# seletor.net
KiCad netlist of a schematic drawn in EAGLE
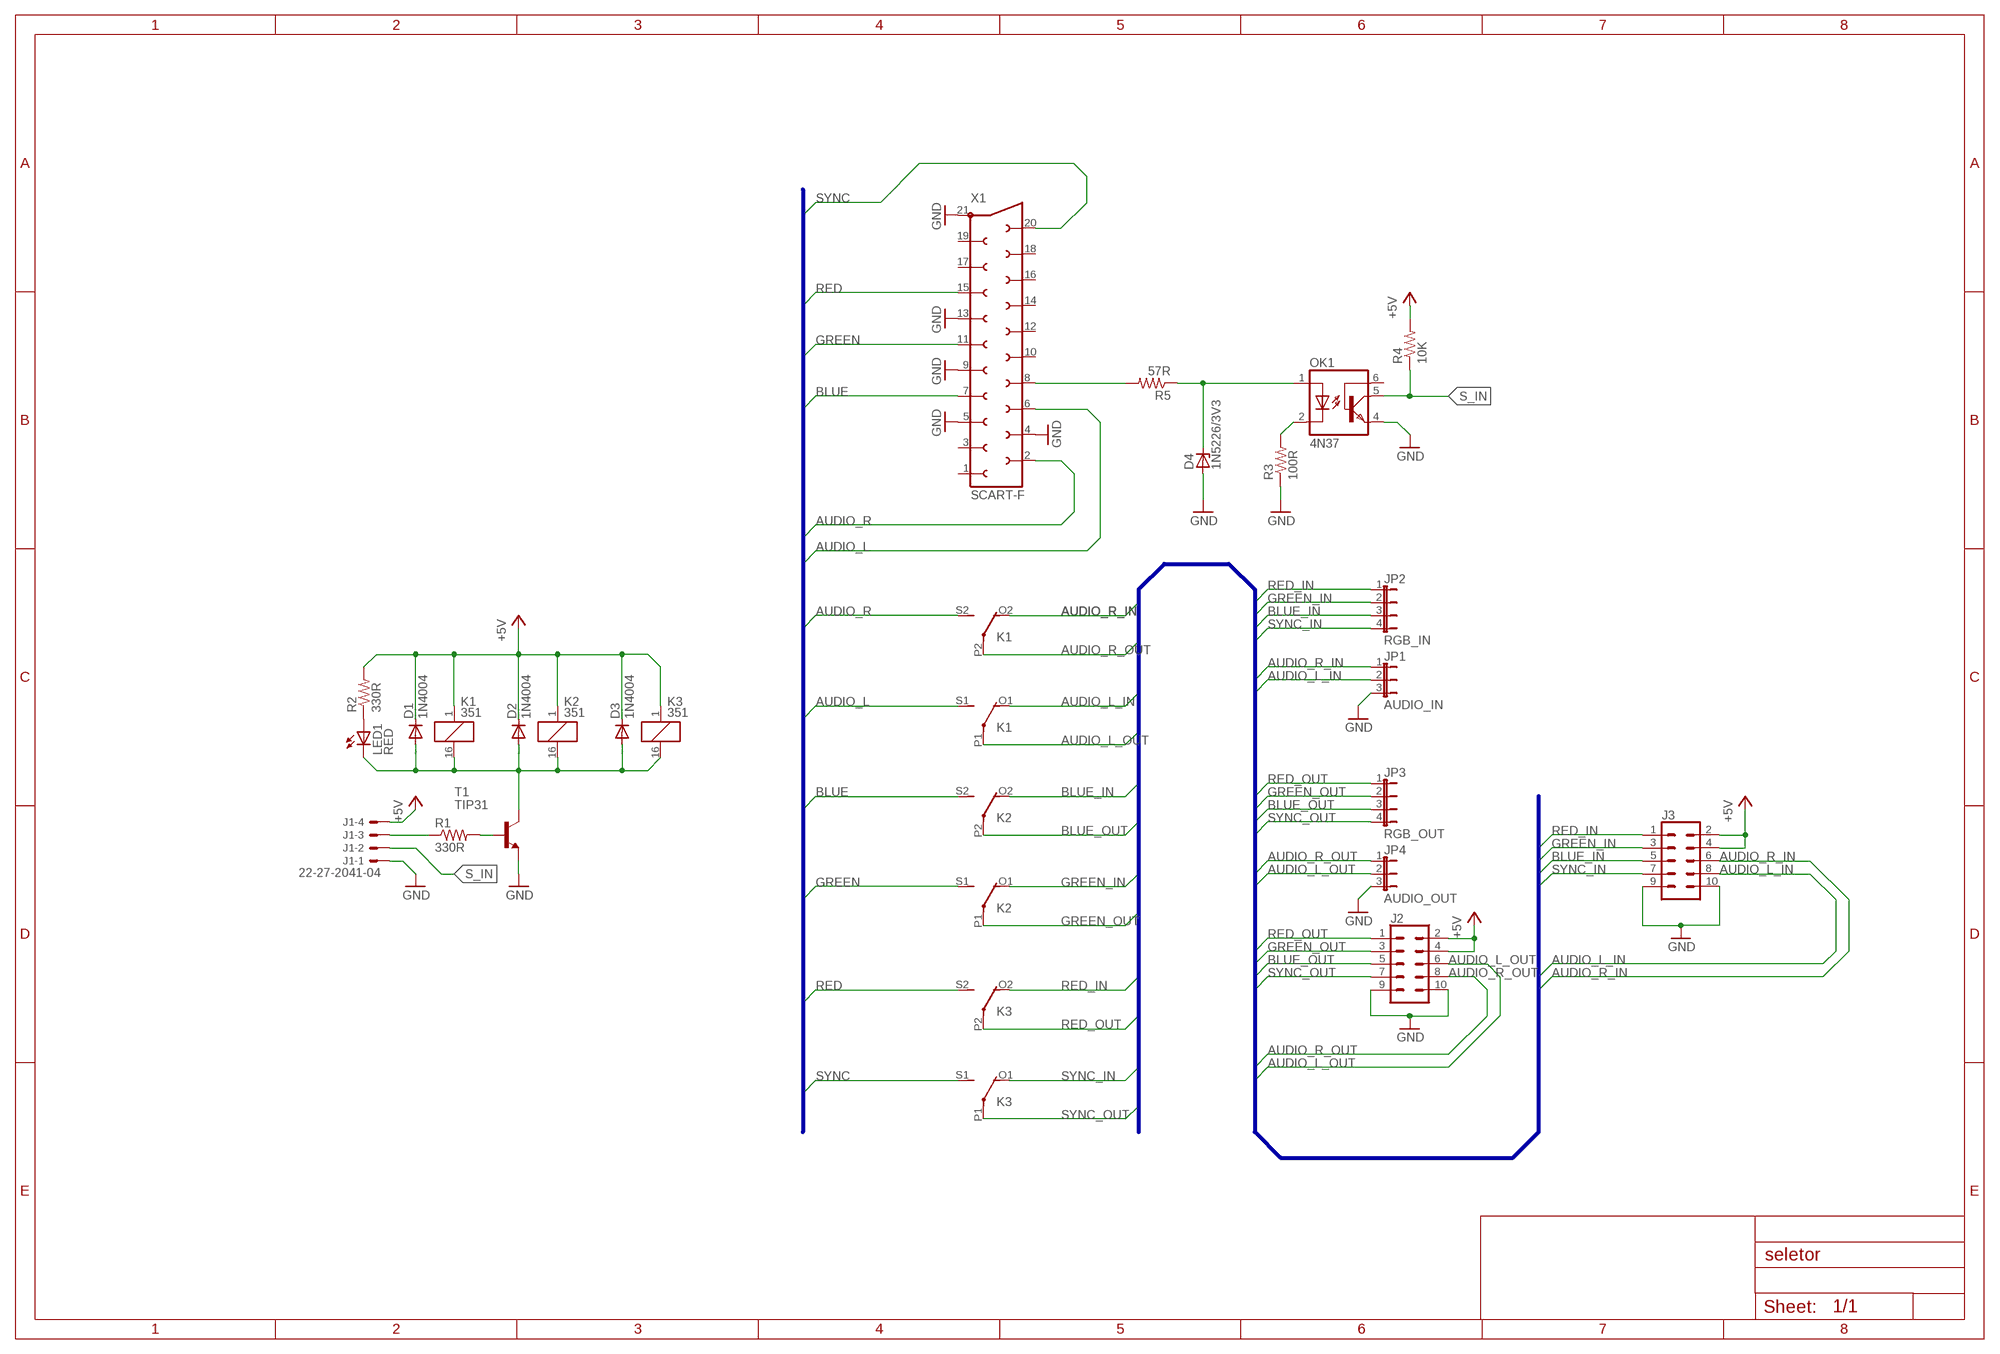
[diagram p0: schematic, sheet 1]

(export (version "E")
  (design (tool "Eeschema 10.0.6"))
  (components
    (comp (ref "D1")
      (value "1N4004")
      (footprint "eagle-import:DO41-10")
      (libsource (lib "eagle-import") (part "1N4004"))
    )
    (comp (ref "D2")
      (value "1N4004")
      (footprint "eagle-import:DO41-10")
      (libsource (lib "eagle-import") (part "1N4004"))
    )
    (comp (ref "D3")
      (value "1N4004")
      (footprint "eagle-import:DO41-10")
      (libsource (lib "eagle-import") (part "1N4004"))
    )
    (comp (ref "D4")
      (value "1N5226/3V3")
      (footprint "eagle-import:DO34Z7")
      (libsource (lib "eagle-import") (part "BZX90"))
    )
    (comp (ref "J1")
      (value "22-27-2041-04")
      (footprint "eagle-import:6410-04")
      (libsource (lib "eagle-import") (part "22-?-0427-2041"))
    )
    (comp (ref "J2")
      (value "CONN_05X2SHD-NS")
      (footprint "eagle-import:2X5-SHROUDED-NS")
      (libsource (lib "eagle-import") (part "CONN_05X2SHD-NS"))
    )
    (comp (ref "J3")
      (value "CONN_05X2SHD-NS")
      (footprint "eagle-import:2X5-SHROUDED-NS")
      (libsource (lib "eagle-import") (part "CONN_05X2SHD-NS"))
    )
    (comp (ref "JP1")
      (value "AUDIO_IN")
      (footprint "eagle-import:JP2")
      (libsource (lib "eagle-import") (part "JP2E"))
    )
    (comp (ref "JP2")
      (value "RGB_IN")
      (footprint "eagle-import:JP4")
      (libsource (lib "eagle-import") (part "JP4E"))
    )
    (comp (ref "JP3")
      (value "RGB_OUT")
      (footprint "eagle-import:JP4")
      (libsource (lib "eagle-import") (part "JP4E"))
    )
    (comp (ref "JP4")
      (value "AUDIO_OUT")
      (footprint "eagle-import:JP2")
      (libsource (lib "eagle-import") (part "JP2E"))
    )
    (comp (ref "K1")
      (value "351")
      (footprint "eagle-import:351")
      (libsource (lib "eagle-import") (part "351"))
    )
    (comp (ref "K2")
      (value "351")
      (footprint "eagle-import:351")
      (libsource (lib "eagle-import") (part "351"))
    )
    (comp (ref "K3")
      (value "351")
      (footprint "eagle-import:351")
      (libsource (lib "eagle-import") (part "351"))
    )
    (comp (ref "LED1")
      (value "RED")
      (footprint "eagle-import:LED5MM")
      (libsource (lib "eagle-import") (part "LED5MM"))
    )
    (comp (ref "OK1")
      (value "4N37")
      (footprint "eagle-import:DIL06")
      (fields (field (name "MF") "FAIRCHILD SEMICONDUCTOR"))
      (libsource (lib "eagle-import") (part "4N37"))
    )
    (comp (ref "R1")
      (value "330R")
      (footprint "eagle-import:0204_7")
      (libsource (lib "eagle-import") (part "R-US_0204/7"))
    )
    (comp (ref "R2")
      (value "330R")
      (footprint "eagle-import:0204_7")
      (libsource (lib "eagle-import") (part "R-US_0204/7"))
    )
    (comp (ref "R3")
      (value "100R")
      (footprint "eagle-import:0204_7")
      (libsource (lib "eagle-import") (part "resistor_R-US_0204/7"))
    )
    (comp (ref "R4")
      (value "10K")
      (footprint "eagle-import:0204_7")
      (libsource (lib "eagle-import") (part "resistor_R-US_0204/7"))
    )
    (comp (ref "R5")
      (value "57R")
      (footprint "eagle-import:0204_7")
      (libsource (lib "eagle-import") (part "R-US_0204/7"))
    )
    (comp (ref "T1")
      (value "TIP31")
      (footprint "eagle-import:TO220")
      (libsource (lib "eagle-import") (part "TIP31"))
    )
    (comp (ref "X1")
      (value "SCART-F")
      (footprint "eagle-import:SCART-F")
      (libsource (lib "eagle-import") (part "SCART-F"))
    )
  )
  (nets
    (net (code "1") (name "+5V") (class "Default")
      (node (ref "D1") (pin "C") (pinfunction "C_C") (pintype "passive"))
      (node (ref "D2") (pin "C") (pinfunction "C_C") (pintype "passive"))
      (node (ref "D3") (pin "C") (pinfunction "C_C") (pintype "passive"))
      (node (ref "J1") (pin "4") (pinfunction "S_4") (pintype "passive"))
      (node (ref "J2") (pin "2") (pinfunction "2_2") (pintype "passive"))
      (node (ref "J2") (pin "4") (pinfunction "4_4") (pintype "passive"))
      (node (ref "J3") (pin "2") (pinfunction "2_2") (pintype "passive"))
      (node (ref "J3") (pin "4") (pinfunction "4_4") (pintype "passive"))
      (node (ref "K1") (pin "1") (pinfunction "1_1") (pintype "passive"))
      (node (ref "K2") (pin "1") (pinfunction "1_1") (pintype "passive"))
      (node (ref "K3") (pin "1") (pinfunction "1_1") (pintype "passive"))
      (node (ref "R2") (pin "2") (pinfunction "2_2") (pintype "passive"))
      (node (ref "R4") (pin "2") (pinfunction "2_2") (pintype "passive"))
    )
    (net (code "2") (name "/AUDIO_L") (class "Default")
      (node (ref "K1") (pin "S1") (pinfunction "S_S1") (pintype "passive"))
      (node (ref "X1") (pin "6") (pinfunction "6_6") (pintype "passive"))
    )
    (net (code "3") (name "/AUDIO_L_IN") (class "Default")
      (node (ref "J3") (pin "8") (pinfunction "8_8") (pintype "passive"))
      (node (ref "JP1") (pin "2") (pinfunction "2_2") (pintype "passive"))
      (node (ref "K1") (pin "O1") (pinfunction "O_O1") (pintype "passive"))
    )
    (net (code "4") (name "/AUDIO_L_OUT") (class "Default")
      (node (ref "J2") (pin "6") (pinfunction "6_6") (pintype "passive"))
      (node (ref "JP4") (pin "2") (pinfunction "2_2") (pintype "passive"))
      (node (ref "K1") (pin "P1") (pinfunction "P_P1") (pintype "passive"))
    )
    (net (code "5") (name "/AUDIO_R") (class "Default")
      (node (ref "K1") (pin "S2") (pinfunction "S_S2") (pintype "passive"))
      (node (ref "X1") (pin "2") (pinfunction "2_2") (pintype "passive"))
    )
    (net (code "6") (name "/AUDIO_R_IN") (class "Default")
      (node (ref "J3") (pin "6") (pinfunction "6_6") (pintype "passive"))
      (node (ref "JP1") (pin "1") (pinfunction "1_1") (pintype "passive"))
      (node (ref "K1") (pin "O2") (pinfunction "O_O2") (pintype "passive"))
    )
    (net (code "7") (name "/AUDIO_R_OUT") (class "Default")
      (node (ref "J2") (pin "8") (pinfunction "8_8") (pintype "passive"))
      (node (ref "JP4") (pin "1") (pinfunction "1_1") (pintype "passive"))
      (node (ref "K1") (pin "P2") (pinfunction "P_P2") (pintype "passive"))
    )
    (net (code "8") (name "/BLUE") (class "Default")
      (node (ref "K2") (pin "S2") (pinfunction "S_S2") (pintype "passive"))
      (node (ref "X1") (pin "7") (pinfunction "7_7") (pintype "passive"))
    )
    (net (code "9") (name "/BLUE_IN") (class "Default")
      (node (ref "J3") (pin "5") (pinfunction "5_5") (pintype "passive"))
      (node (ref "JP2") (pin "3") (pinfunction "3_3") (pintype "passive"))
      (node (ref "K2") (pin "O2") (pinfunction "O_O2") (pintype "passive"))
    )
    (net (code "10") (name "/BLUE_OUT") (class "Default")
      (node (ref "J2") (pin "5") (pinfunction "5_5") (pintype "passive"))
      (node (ref "JP3") (pin "3") (pinfunction "3_3") (pintype "passive"))
      (node (ref "K2") (pin "P2") (pinfunction "P_P2") (pintype "passive"))
    )
    (net (code "11") (name "/GREEN") (class "Default")
      (node (ref "K2") (pin "S1") (pinfunction "S_S1") (pintype "passive"))
      (node (ref "X1") (pin "11") (pinfunction "11_11") (pintype "passive"))
    )
    (net (code "12") (name "/GREEN_IN") (class "Default")
      (node (ref "J3") (pin "3") (pinfunction "3_3") (pintype "passive"))
      (node (ref "JP2") (pin "2") (pinfunction "2_2") (pintype "passive"))
      (node (ref "K2") (pin "O1") (pinfunction "O_O1") (pintype "passive"))
    )
    (net (code "13") (name "/GREEN_OUT") (class "Default")
      (node (ref "J2") (pin "3") (pinfunction "3_3") (pintype "passive"))
      (node (ref "JP3") (pin "2") (pinfunction "2_2") (pintype "passive"))
      (node (ref "K2") (pin "P1") (pinfunction "P_P1") (pintype "passive"))
    )
    (net (code "14") (name "/RED") (class "Default")
      (node (ref "K3") (pin "S2") (pinfunction "S_S2") (pintype "passive"))
      (node (ref "X1") (pin "15") (pinfunction "15_15") (pintype "passive"))
    )
    (net (code "15") (name "/RED_IN") (class "Default")
      (node (ref "J3") (pin "1") (pinfunction "1_1") (pintype "passive"))
      (node (ref "JP2") (pin "1") (pinfunction "1_1") (pintype "passive"))
      (node (ref "K3") (pin "O2") (pinfunction "O_O2") (pintype "passive"))
    )
    (net (code "16") (name "/RED_OUT") (class "Default")
      (node (ref "J2") (pin "1") (pinfunction "1_1") (pintype "passive"))
      (node (ref "JP3") (pin "1") (pinfunction "1_1") (pintype "passive"))
      (node (ref "K3") (pin "P2") (pinfunction "P_P2") (pintype "passive"))
    )
    (net (code "17") (name "/SYNC") (class "Default")
      (node (ref "K3") (pin "S1") (pinfunction "S_S1") (pintype "passive"))
      (node (ref "X1") (pin "20") (pinfunction "20_20") (pintype "passive"))
    )
    (net (code "18") (name "/SYNC_IN") (class "Default")
      (node (ref "J3") (pin "7") (pinfunction "7_7") (pintype "passive"))
      (node (ref "JP2") (pin "4") (pinfunction "4_4") (pintype "passive"))
      (node (ref "K3") (pin "O1") (pinfunction "O_O1") (pintype "passive"))
    )
    (net (code "19") (name "/SYNC_OUT") (class "Default")
      (node (ref "J2") (pin "7") (pinfunction "7_7") (pintype "passive"))
      (node (ref "JP3") (pin "4") (pinfunction "4_4") (pintype "passive"))
      (node (ref "K3") (pin "P1") (pinfunction "P_P1") (pintype "passive"))
    )
    (net (code "20") (name "GND") (class "Default")
      (node (ref "D4") (pin "A") (pinfunction "A_A") (pintype "passive"))
      (node (ref "J1") (pin "1") (pinfunction "S_1") (pintype "passive"))
      (node (ref "J2") (pin "10") (pinfunction "10_10") (pintype "passive"))
      (node (ref "J2") (pin "9") (pinfunction "9_9") (pintype "passive"))
      (node (ref "J3") (pin "10") (pinfunction "10_10") (pintype "passive"))
      (node (ref "J3") (pin "9") (pinfunction "9_9") (pintype "passive"))
      (node (ref "JP1") (pin "3") (pinfunction "3_3") (pintype "passive"))
      (node (ref "JP4") (pin "3") (pinfunction "3_3") (pintype "passive"))
      (node (ref "OK1") (pin "4") (pinfunction "EMI_4") (pintype "passive"))
      (node (ref "R3") (pin "1") (pinfunction "1_1") (pintype "passive"))
      (node (ref "T1") (pin "3") (pinfunction "E_3") (pintype "passive"))
      (node (ref "X1") (pin "13") (pinfunction "13_13") (pintype "passive"))
      (node (ref "X1") (pin "21") (pinfunction "21_21") (pintype "passive"))
      (node (ref "X1") (pin "4") (pinfunction "4_4") (pintype "passive"))
      (node (ref "X1") (pin "5") (pinfunction "5_5") (pintype "passive"))
      (node (ref "X1") (pin "9") (pinfunction "9_9") (pintype "passive"))
    )
    (net (code "21") (name "Net-(J1C-S)") (class "Default")
      (node (ref "J1") (pin "3") (pinfunction "S_3") (pintype "passive"))
      (node (ref "R1") (pin "1") (pinfunction "1_1") (pintype "passive"))
    )
    (net (code "22") (name "Net-(K1A-2)") (class "Default")
      (node (ref "D1") (pin "A") (pinfunction "A_A") (pintype "passive"))
      (node (ref "D2") (pin "A") (pinfunction "A_A") (pintype "passive"))
      (node (ref "D3") (pin "A") (pinfunction "A_A") (pintype "passive"))
      (node (ref "K1") (pin "16") (pinfunction "2_16") (pintype "passive"))
      (node (ref "K2") (pin "16") (pinfunction "2_16") (pintype "passive"))
      (node (ref "K3") (pin "16") (pinfunction "2_16") (pintype "passive"))
      (node (ref "LED1") (pin "K") (pinfunction "C_K") (pintype "passive"))
      (node (ref "T1") (pin "2") (pinfunction "C_2") (pintype "passive"))
    )
    (net (code "23") (name "Net-(LED1-PadA)") (class "Default")
      (node (ref "LED1") (pin "A") (pinfunction "A_A") (pintype "passive"))
      (node (ref "R2") (pin "1") (pinfunction "1_1") (pintype "passive"))
    )
    (net (code "24") (name "Net-(OK1-A)") (class "Default")
      (node (ref "D4") (pin "C") (pinfunction "C_C") (pintype "passive"))
      (node (ref "OK1") (pin "1") (pinfunction "A_1") (pintype "passive"))
      (node (ref "R5") (pin "1") (pinfunction "1_1") (pintype "passive"))
    )
    (net (code "25") (name "Net-(OK1-C)") (class "Default")
      (node (ref "OK1") (pin "2") (pinfunction "C_2") (pintype "passive"))
      (node (ref "R3") (pin "2") (pinfunction "2_2") (pintype "passive"))
    )
    (net (code "26") (name "Net-(R5-Pad2)") (class "Default")
      (node (ref "R5") (pin "2") (pinfunction "2_2") (pintype "passive"))
      (node (ref "X1") (pin "8") (pinfunction "8_8") (pintype "passive"))
    )
    (net (code "27") (name "Net-(T1-B)") (class "Default")
      (node (ref "R1") (pin "2") (pinfunction "2_2") (pintype "passive"))
      (node (ref "T1") (pin "1") (pinfunction "B_1") (pintype "passive"))
    )
    (net (code "28") (name "S_IN") (class "Default")
      (node (ref "J1") (pin "2") (pinfunction "S_2") (pintype "passive"))
      (node (ref "OK1") (pin "5") (pinfunction "COL_5") (pintype "passive"))
      (node (ref "R4") (pin "1") (pinfunction "1_1") (pintype "passive"))
    )
    (net (code "29") (name "unconnected-(OK1-BAS-Pad6)") (class "Default")
      (node (ref "OK1") (pin "6") (pinfunction "BAS_6") (pintype "passive"))
    )
    (net (code "30") (name "unconnected-(X1-Pad1)") (class "Default")
      (node (ref "X1") (pin "1") (pinfunction "1_1") (pintype "passive"))
    )
    (net (code "31") (name "unconnected-(X1-Pad3)") (class "Default")
      (node (ref "X1") (pin "3") (pinfunction "3_3") (pintype "passive"))
    )
    (net (code "32") (name "unconnected-(X1-Pad10)") (class "Default")
      (node (ref "X1") (pin "10") (pinfunction "10_10") (pintype "passive"))
    )
    (net (code "33") (name "unconnected-(X1-Pad12)") (class "Default")
      (node (ref "X1") (pin "12") (pinfunction "12_12") (pintype "passive"))
    )
    (net (code "34") (name "unconnected-(X1-Pad14)") (class "Default")
      (node (ref "X1") (pin "14") (pinfunction "14_14") (pintype "passive"))
    )
    (net (code "35") (name "unconnected-(X1-Pad16)") (class "Default")
      (node (ref "X1") (pin "16") (pinfunction "16_16") (pintype "passive"))
    )
    (net (code "36") (name "unconnected-(X1-Pad17)") (class "Default")
      (node (ref "X1") (pin "17") (pinfunction "17_17") (pintype "passive"))
    )
    (net (code "37") (name "unconnected-(X1-Pad18)") (class "Default")
      (node (ref "X1") (pin "18") (pinfunction "18_18") (pintype "passive"))
    )
    (net (code "38") (name "unconnected-(X1-Pad19)") (class "Default")
      (node (ref "X1") (pin "19") (pinfunction "19_19") (pintype "passive"))
    )
  )
)
